# controller_rev1_1_flat.net
KiCad netlist of a schematic drawn in EAGLE
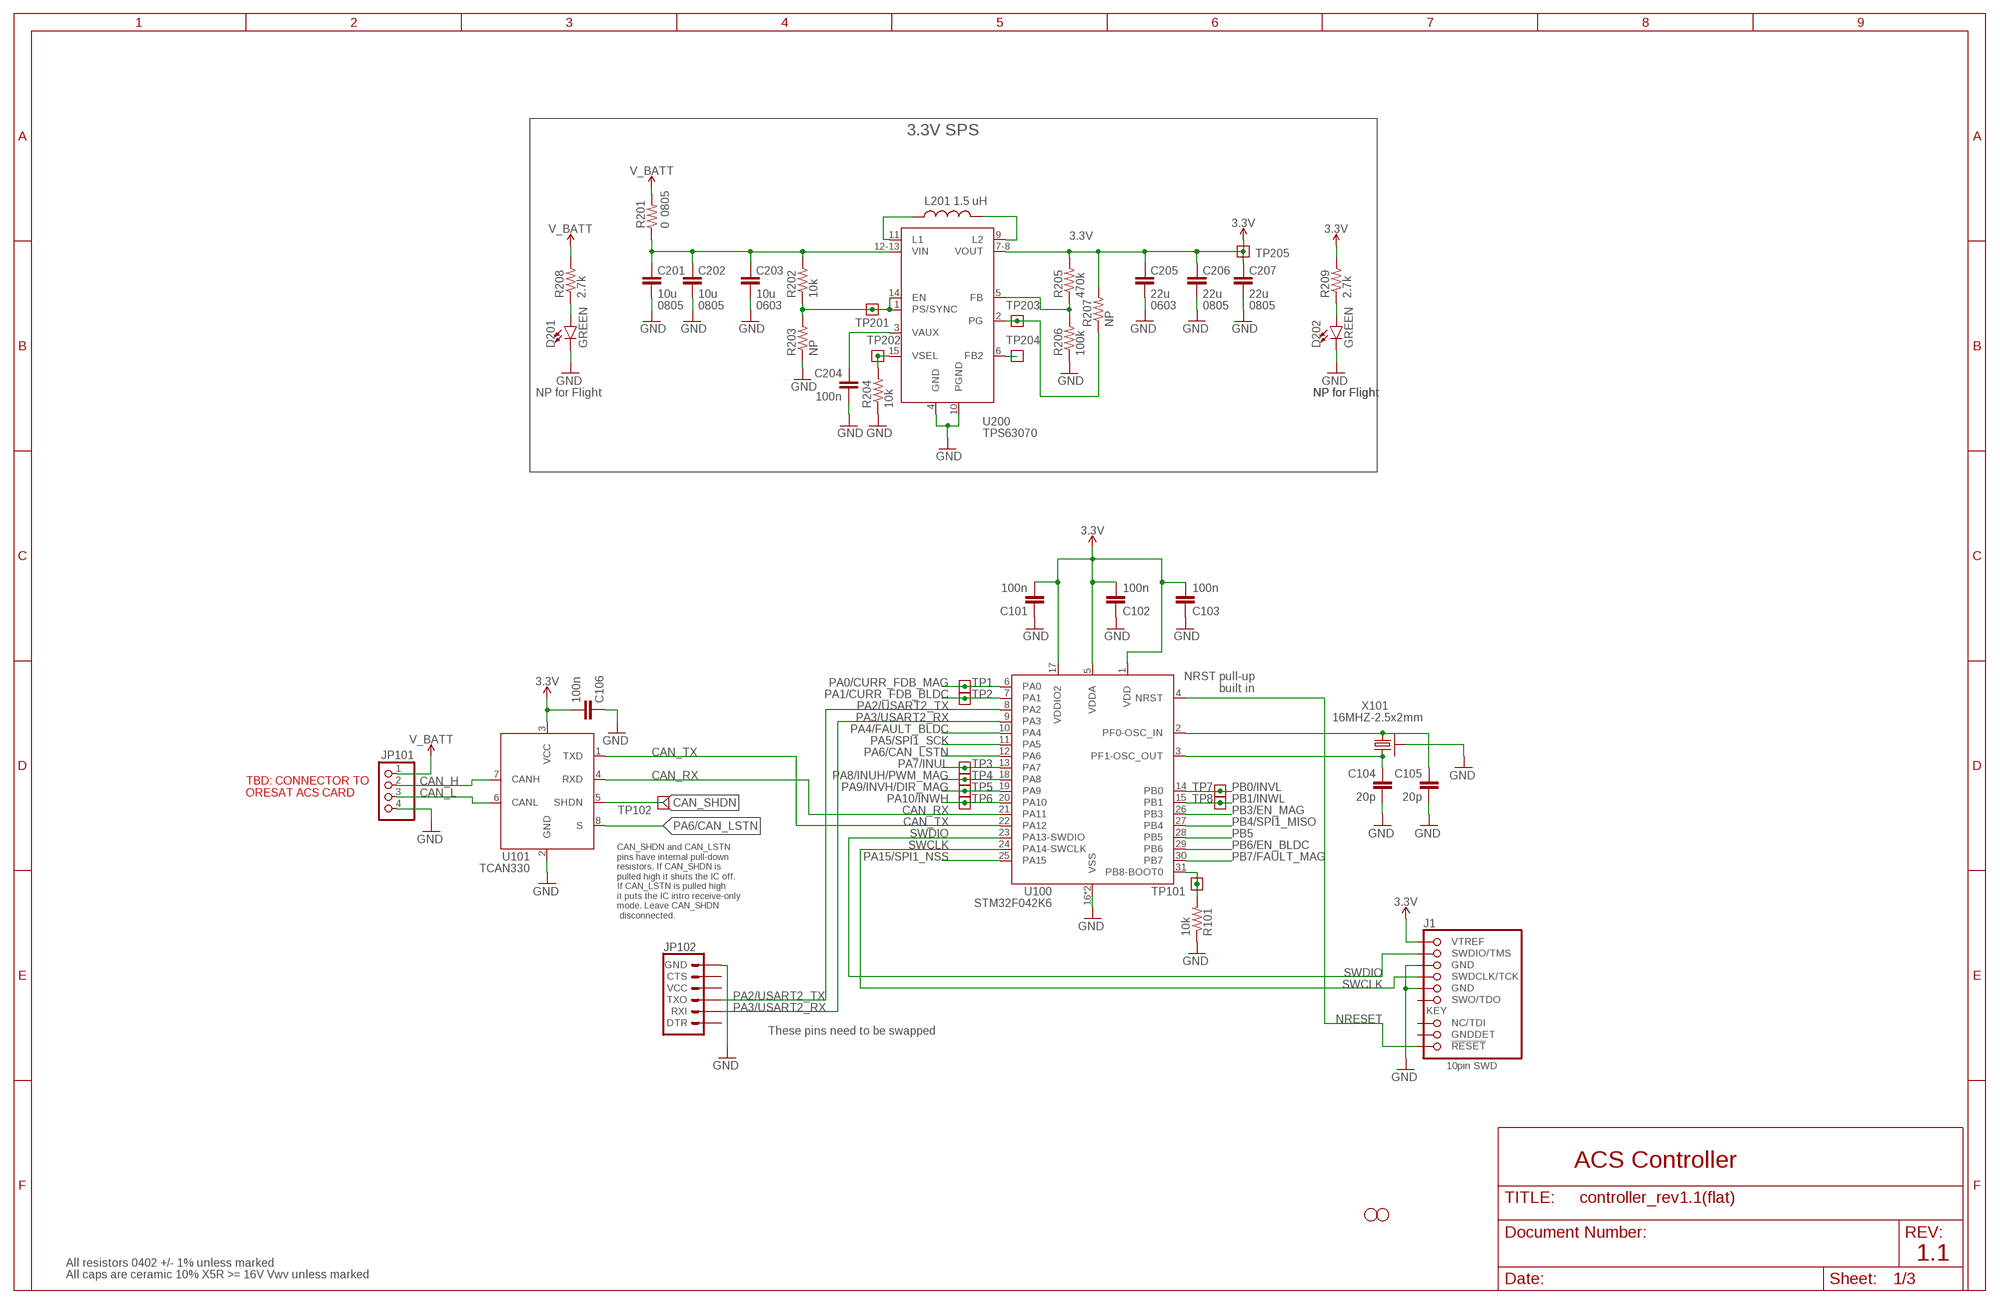
[diagram p0: schematic, sheet 1]
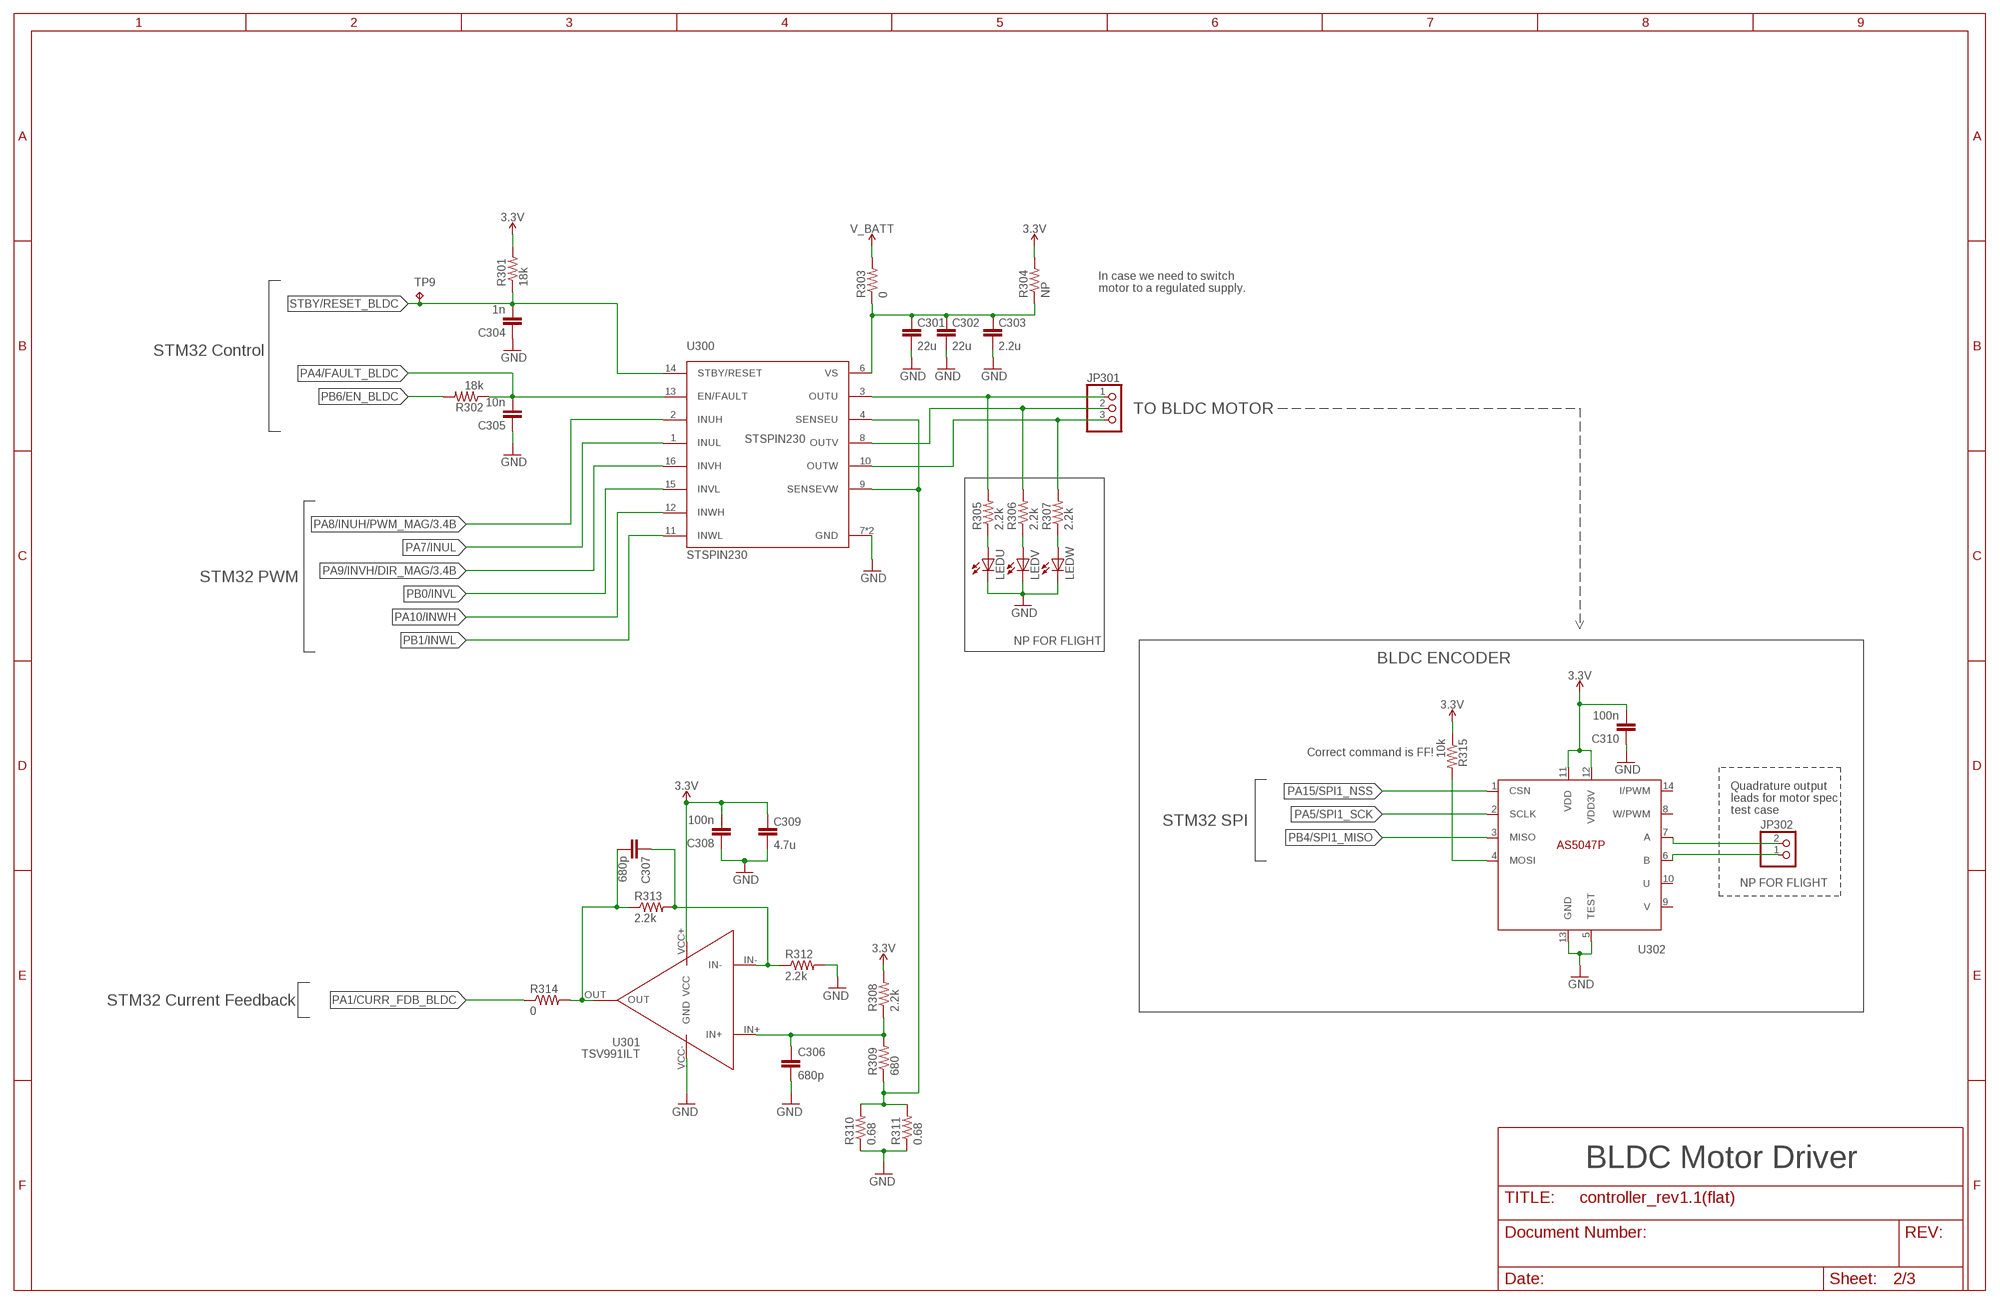
[diagram p1: schematic, sheet 2]
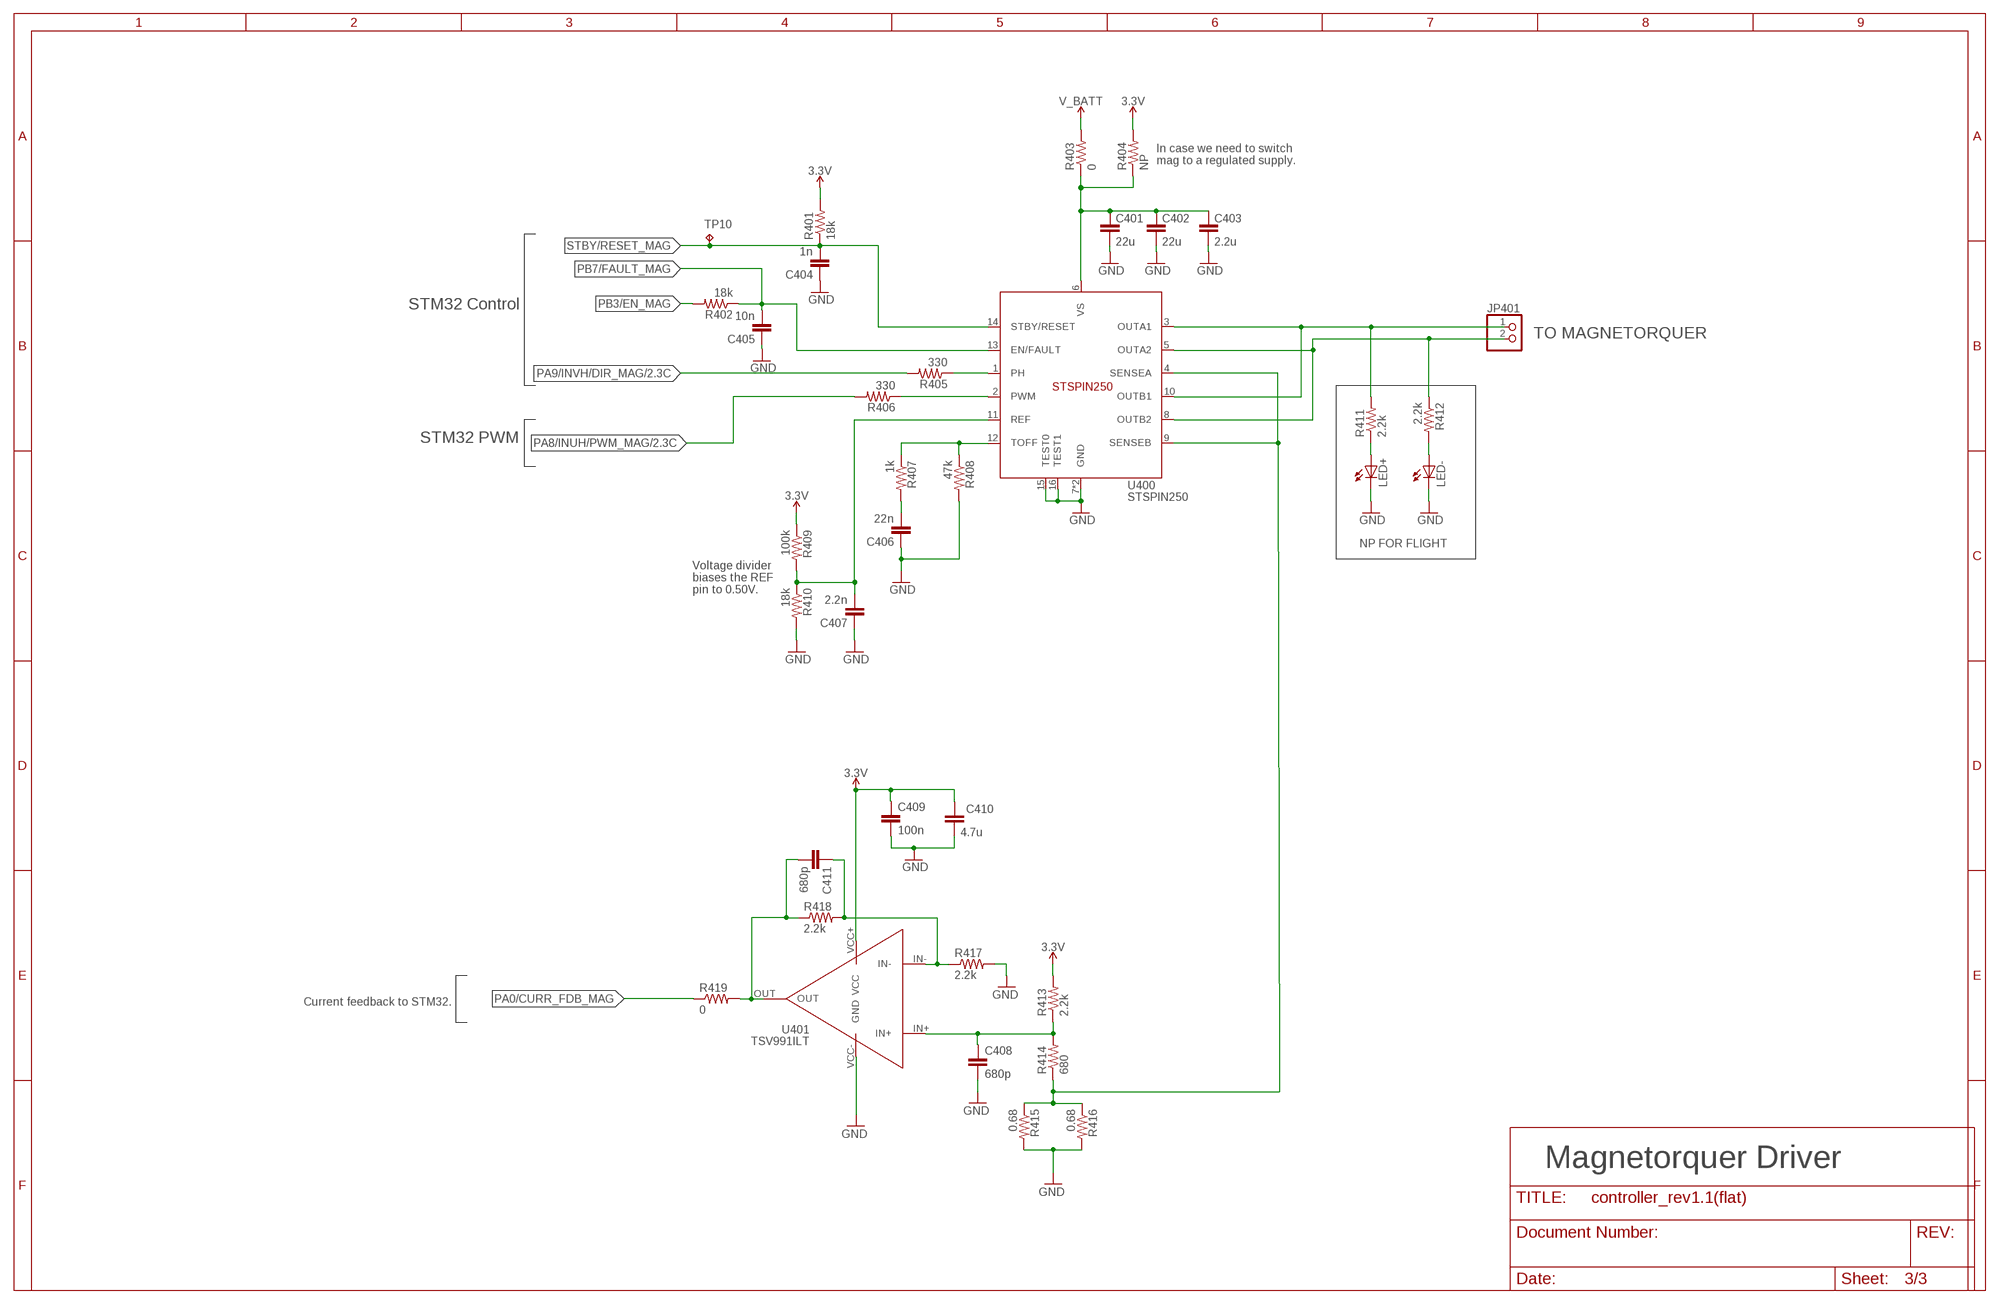
[diagram p2: schematic, sheet 3]

(export (version "E")
  (design (tool "Eeschema 10.0.6"))
  (components
    (comp (ref "C301")
      (value "22u")
      (footprint "eagle-import:.0603-B-NOSILK")
      (fields (field (name "MFR") "Samsung") (field (name "MPN") "CL05B104KO5NNNC"))
      (libsource (lib "eagle-import") (part "C-EU0603-B-NOSILK"))
    )
    (comp (ref "C302")
      (value "22u")
      (footprint "eagle-import:.0603-B-NOSILK")
      (fields (field (name "MFR") "Samsung") (field (name "MPN") "CL05B104KO5NNNC"))
      (libsource (lib "eagle-import") (part "C-EU0603-B-NOSILK"))
    )
    (comp (ref "C303")
      (value "2.2u")
      (footprint "eagle-import:.0603-B-NOSILK")
      (fields (field (name "MFR") "Samsung") (field (name "MPN") "CL05B104KO5NNNC"))
      (libsource (lib "eagle-import") (part "C-EU0603-B-NOSILK"))
    )
    (comp (ref "C304")
      (value "1n")
      (footprint "eagle-import:.0402-B-NOSILK")
      (fields (field (name "MFR") "Samsung") (field (name "MPN") "CL05B104KO5NNNC"))
      (libsource (lib "eagle-import") (part "rcl_custom_C-EU0402-B-NOSILK"))
    )
    (comp (ref "C305")
      (value "10n")
      (footprint "eagle-import:.0402-B-NOSILK")
      (fields (field (name "MFR") "Samsung") (field (name "MPN") "CL05B104KO5NNNC"))
      (libsource (lib "eagle-import") (part "rcl_custom_C-EU0402-B-NOSILK"))
    )
    (comp (ref "C306")
      (value "680p")
      (footprint "eagle-import:.0402-B-NOSILK")
      (fields (field (name "MFR") "Samsung") (field (name "MPN") "CL05B104KO5NNNC"))
      (libsource (lib "eagle-import") (part "rcl_custom_C-EU0402-B-NOSILK"))
    )
    (comp (ref "C307")
      (value "680p")
      (footprint "eagle-import:.0402-B-NOSILK")
      (fields (field (name "MFR") "Samsung") (field (name "MPN") "CL05B104KO5NNNC"))
      (libsource (lib "eagle-import") (part "rcl_custom_C-EU0402-B-NOSILK"))
    )
    (comp (ref "C308")
      (value "100n")
      (footprint "eagle-import:.0402-B-NOSILK")
      (fields (field (name "MFR") "Samsung") (field (name "MPN") "CL05B104KO5NNNC"))
      (libsource (lib "eagle-import") (part "rcl_custom_C-EU0402-B-NOSILK"))
    )
    (comp (ref "C309")
      (value "4.7u")
      (footprint "eagle-import:.0603-B-NOSILK")
      (fields (field (name "MFR") "Samsung") (field (name "MPN") "CL05B104KO5NNNC"))
      (libsource (lib "eagle-import") (part "C-EU0603-B-NOSILK"))
    )
    (comp (ref "C310")
      (value "100n")
      (footprint "eagle-import:.0402-B-NOSILK")
      (fields (field (name "MFR") "Samsung") (field (name "MPN") "CL05B104KO5NNNC"))
      (libsource (lib "eagle-import") (part "rcl_custom_C-EU0402-B-NOSILK"))
    )
    (comp (ref "JP301")
      (value "PINHD-1X3")
      (footprint "eagle-import:1X03")
      (libsource (lib "eagle-import") (part "PINHD-1X3"))
    )
    (comp (ref "JP302")
      (value "PINHD-1X2/90")
      (footprint "eagle-import:1X02_90")
      (libsource (lib "eagle-import") (part "PINHD-1X2/90"))
    )
    (comp (ref "LEDU")
      (value "LEDCHIP-LED0603")
      (footprint "eagle-import:CHIP-LED0603")
      (libsource (lib "eagle-import") (part "LEDCHIP-LED0603"))
    )
    (comp (ref "LEDV")
      (value "LEDCHIP-LED0603")
      (footprint "eagle-import:CHIP-LED0603")
      (libsource (lib "eagle-import") (part "LEDCHIP-LED0603"))
    )
    (comp (ref "LEDW")
      (value "LEDCHIP-LED0603")
      (footprint "eagle-import:CHIP-LED0603")
      (libsource (lib "eagle-import") (part "LEDCHIP-LED0603"))
    )
    (comp (ref "R301")
      (value "18k")
      (footprint "eagle-import:.0402-B-NOSILK")
      (fields (field (name "MFR") "Samsung") (field (name "MPN") "RC1005F6653CS"))
      (libsource (lib "eagle-import") (part "rcl_custom_R-US_0402-B-NOSILK"))
    )
    (comp (ref "R302")
      (value "18k")
      (footprint "eagle-import:.0402-B-NOSILK")
      (fields (field (name "MFR") "Samsung") (field (name "MPN") "RC1005F6653CS"))
      (libsource (lib "eagle-import") (part "rcl_custom_R-US_0402-B-NOSILK"))
    )
    (comp (ref "R303")
      (value "0")
      (footprint "eagle-import:.0805-B-NOSILK")
      (libsource (lib "eagle-import") (part "R-US_0805-B-NOSILK"))
    )
    (comp (ref "R304")
      (value "NP")
      (footprint "eagle-import:.0805-B-NOSILK")
      (libsource (lib "eagle-import") (part "R-US_0805-B-NOSILK"))
    )
    (comp (ref "R305")
      (value "2.2k")
      (footprint "eagle-import:.0805-B-NOSILK")
      (libsource (lib "eagle-import") (part "R-US_0805-B-NOSILK"))
    )
    (comp (ref "R306")
      (value "2.2k")
      (footprint "eagle-import:.0805-B-NOSILK")
      (libsource (lib "eagle-import") (part "R-US_0805-B-NOSILK"))
    )
    (comp (ref "R307")
      (value "2.2k")
      (footprint "eagle-import:.0805-B-NOSILK")
      (libsource (lib "eagle-import") (part "R-US_0805-B-NOSILK"))
    )
    (comp (ref "R308")
      (value "2.2k")
      (footprint "eagle-import:.0402-B-NOSILK")
      (fields (field (name "MFR") "Samsung") (field (name "MPN") "RC1005F6653CS"))
      (libsource (lib "eagle-import") (part "rcl_custom_R-US_0402-B-NOSILK"))
    )
    (comp (ref "R309")
      (value "680")
      (footprint "eagle-import:.0402-B-NOSILK")
      (fields (field (name "MFR") "Samsung") (field (name "MPN") "RC1005F6653CS"))
      (libsource (lib "eagle-import") (part "rcl_custom_R-US_0402-B-NOSILK"))
    )
    (comp (ref "R310")
      (value "0.68")
      (footprint "eagle-import:.0805-B-NOSILK")
      (libsource (lib "eagle-import") (part "R-US_0805-B-NOSILK"))
    )
    (comp (ref "R311")
      (value "0.68")
      (footprint "eagle-import:.0805-B-NOSILK")
      (libsource (lib "eagle-import") (part "R-US_0805-B-NOSILK"))
    )
    (comp (ref "R312")
      (value "2.2k")
      (footprint "eagle-import:.0402-B-NOSILK")
      (fields (field (name "MFR") "Samsung") (field (name "MPN") "RC1005F6653CS"))
      (libsource (lib "eagle-import") (part "rcl_custom_R-US_0402-B-NOSILK"))
    )
    (comp (ref "R313")
      (value "2.2k")
      (footprint "eagle-import:.0402-B-NOSILK")
      (fields (field (name "MFR") "Samsung") (field (name "MPN") "RC1005F6653CS"))
      (libsource (lib "eagle-import") (part "rcl_custom_R-US_0402-B-NOSILK"))
    )
    (comp (ref "R314")
      (value "0")
      (footprint "eagle-import:.0402-B-NOSILK")
      (fields (field (name "MFR") "Samsung") (field (name "MPN") "RC1005F6653CS"))
      (libsource (lib "eagle-import") (part "rcl_custom_R-US_0402-B-NOSILK"))
    )
    (comp (ref "R315")
      (value "10k")
      (footprint "eagle-import:.0402-B-NOSILK")
      (fields (field (name "MFR") "Samsung") (field (name "MPN") "RC1005F6653CS"))
      (libsource (lib "eagle-import") (part "rcl_custom_R-US_0402-B-NOSILK"))
    )
    (comp (ref "TP9")
      (value "TPPAD1-13")
      (footprint "eagle-import:P1-13")
      (libsource (lib "eagle-import") (part "TPPAD1-13"))
    )
    (comp (ref "U300")
      (value "STSPIN230")
      (footprint "eagle-import:VFQFPN")
      (libsource (lib "eagle-import") (part "STSPIN230"))
    )
    (comp (ref "U301")
      (value "TSV991ILT")
      (footprint "eagle-import:SOT23-5")
      (libsource (lib "eagle-import") (part "TSV991ILT"))
    )
    (comp (ref "U302")
      (value "AS5047P")
      (footprint "eagle-import:TSSOP14")
      (libsource (lib "eagle-import") (part "AS5047P"))
    )
    (comp (ref "C401")
      (value "22u")
      (footprint "eagle-import:.0603-B-NOSILK")
      (fields (field (name "MFR") "Samsung") (field (name "MPN") "CL05B104KO5NNNC"))
      (libsource (lib "eagle-import") (part "C-EU0603-B-NOSILK"))
    )
    (comp (ref "C402")
      (value "22u")
      (footprint "eagle-import:.0603-B-NOSILK")
      (fields (field (name "MFR") "Samsung") (field (name "MPN") "CL05B104KO5NNNC"))
      (libsource (lib "eagle-import") (part "C-EU0603-B-NOSILK"))
    )
    (comp (ref "C403")
      (value "2.2u")
      (footprint "eagle-import:.0603-B-NOSILK")
      (fields (field (name "MFR") "Samsung") (field (name "MPN") "CL05B104KO5NNNC"))
      (libsource (lib "eagle-import") (part "C-EU0603-B-NOSILK"))
    )
    (comp (ref "C404")
      (value "1n")
      (footprint "eagle-import:.0402-B-NOSILK")
      (fields (field (name "MFR") "Samsung") (field (name "MPN") "CL05B104KO5NNNC"))
      (libsource (lib "eagle-import") (part "rcl_custom_C-EU0402-B-NOSILK"))
    )
    (comp (ref "C405")
      (value "10n")
      (footprint "eagle-import:.0402-B-NOSILK")
      (fields (field (name "MFR") "Samsung") (field (name "MPN") "CL05B104KO5NNNC"))
      (libsource (lib "eagle-import") (part "rcl_custom_C-EU0402-B-NOSILK"))
    )
    (comp (ref "C406")
      (value "22n")
      (footprint "eagle-import:.0402-B-NOSILK")
      (fields (field (name "MFR") "Samsung") (field (name "MPN") "CL05B104KO5NNNC"))
      (libsource (lib "eagle-import") (part "rcl_custom_C-EU0402-B-NOSILK"))
    )
    (comp (ref "C407")
      (value "2.2n")
      (footprint "eagle-import:.0402-B-NOSILK")
      (fields (field (name "MFR") "Samsung") (field (name "MPN") "CL05B104KO5NNNC"))
      (libsource (lib "eagle-import") (part "rcl_custom_C-EU0402-B-NOSILK"))
    )
    (comp (ref "C408")
      (value "680p")
      (footprint "eagle-import:.0402-B-NOSILK")
      (fields (field (name "MFR") "Samsung") (field (name "MPN") "CL05B104KO5NNNC"))
      (libsource (lib "eagle-import") (part "rcl_custom_C-EU0402-B-NOSILK"))
    )
    (comp (ref "C409")
      (value "100n")
      (footprint "eagle-import:.0402-B-NOSILK")
      (fields (field (name "MFR") "Samsung") (field (name "MPN") "CL05B104KO5NNNC"))
      (libsource (lib "eagle-import") (part "rcl_custom_C-EU0402-B-NOSILK"))
    )
    (comp (ref "C410")
      (value "4.7u")
      (footprint "eagle-import:.0603-B-NOSILK")
      (fields (field (name "MFR") "Samsung") (field (name "MPN") "CL05B104KO5NNNC"))
      (libsource (lib "eagle-import") (part "C-EU0603-B-NOSILK"))
    )
    (comp (ref "C411")
      (value "680p")
      (footprint "eagle-import:.0402-B-NOSILK")
      (fields (field (name "MFR") "Samsung") (field (name "MPN") "CL05B104KO5NNNC"))
      (libsource (lib "eagle-import") (part "rcl_custom_C-EU0402-B-NOSILK"))
    )
    (comp (ref "JP401")
      (value "PINHD-1X2")
      (footprint "eagle-import:1X02")
      (libsource (lib "eagle-import") (part "PINHD-1X2"))
    )
    (comp (ref "LED+")
      (value "LEDCHIP-LED0603")
      (footprint "eagle-import:CHIP-LED0603")
      (libsource (lib "eagle-import") (part "LEDCHIP-LED0603"))
    )
    (comp (ref "LED-")
      (value "LEDCHIP-LED0603")
      (footprint "eagle-import:CHIP-LED0603")
      (libsource (lib "eagle-import") (part "LEDCHIP-LED0603"))
    )
    (comp (ref "R401")
      (value "18k")
      (footprint "eagle-import:.0402-B-NOSILK")
      (fields (field (name "MFR") "Samsung") (field (name "MPN") "RC1005F6653CS"))
      (libsource (lib "eagle-import") (part "rcl_custom_R-US_0402-B-NOSILK"))
    )
    (comp (ref "R402")
      (value "18k")
      (footprint "eagle-import:.0402-B-NOSILK")
      (fields (field (name "MFR") "Samsung") (field (name "MPN") "RC1005F6653CS"))
      (libsource (lib "eagle-import") (part "rcl_custom_R-US_0402-B-NOSILK"))
    )
    (comp (ref "R403")
      (value "0")
      (footprint "eagle-import:.0805-B-NOSILK")
      (libsource (lib "eagle-import") (part "R-US_0805-B-NOSILK"))
    )
    (comp (ref "R404")
      (value "NP")
      (footprint "eagle-import:.0805-B-NOSILK")
      (libsource (lib "eagle-import") (part "R-US_0805-B-NOSILK"))
    )
    (comp (ref "R405")
      (value "330")
      (footprint "eagle-import:.0402-B-NOSILK")
      (fields (field (name "MFR") "Samsung") (field (name "MPN") "RC1005F6653CS"))
      (libsource (lib "eagle-import") (part "rcl_custom_R-US_0402-B-NOSILK"))
    )
    (comp (ref "R406")
      (value "330")
      (footprint "eagle-import:.0402-B-NOSILK")
      (fields (field (name "MFR") "Samsung") (field (name "MPN") "RC1005F6653CS"))
      (libsource (lib "eagle-import") (part "rcl_custom_R-US_0402-B-NOSILK"))
    )
    (comp (ref "R407")
      (value "1k")
      (footprint "eagle-import:.0402-B-NOSILK")
      (fields (field (name "MFR") "Samsung") (field (name "MPN") "RC1005F6653CS"))
      (libsource (lib "eagle-import") (part "rcl_custom_R-US_0402-B-NOSILK"))
    )
    (comp (ref "R408")
      (value "47k")
      (footprint "eagle-import:.0402-B-NOSILK")
      (fields (field (name "MFR") "Samsung") (field (name "MPN") "RC1005F6653CS"))
      (libsource (lib "eagle-import") (part "rcl_custom_R-US_0402-B-NOSILK"))
    )
    (comp (ref "R409")
      (value "100k")
      (footprint "eagle-import:.0402-B-NOSILK")
      (fields (field (name "MFR") "Samsung") (field (name "MPN") "RC1005F6653CS"))
      (libsource (lib "eagle-import") (part "rcl_custom_R-US_0402-B-NOSILK"))
    )
    (comp (ref "R410")
      (value "18k")
      (footprint "eagle-import:.0402-B-NOSILK")
      (fields (field (name "MFR") "Samsung") (field (name "MPN") "RC1005F6653CS"))
      (libsource (lib "eagle-import") (part "rcl_custom_R-US_0402-B-NOSILK"))
    )
    (comp (ref "R411")
      (value "2.2k")
      (footprint "eagle-import:.0805-B-NOSILK")
      (libsource (lib "eagle-import") (part "R-US_0805-B-NOSILK"))
    )
    (comp (ref "R412")
      (value "2.2k")
      (footprint "eagle-import:.0805-B-NOSILK")
      (libsource (lib "eagle-import") (part "R-US_0805-B-NOSILK"))
    )
    (comp (ref "R413")
      (value "2.2k")
      (footprint "eagle-import:.0402-B-NOSILK")
      (fields (field (name "MFR") "Samsung") (field (name "MPN") "RC1005F6653CS"))
      (libsource (lib "eagle-import") (part "rcl_custom_R-US_0402-B-NOSILK"))
    )
    (comp (ref "R414")
      (value "680")
      (footprint "eagle-import:.0402-B-NOSILK")
      (fields (field (name "MFR") "Samsung") (field (name "MPN") "RC1005F6653CS"))
      (libsource (lib "eagle-import") (part "rcl_custom_R-US_0402-B-NOSILK"))
    )
    (comp (ref "R415")
      (value "0.68")
      (footprint "eagle-import:.0805-B-NOSILK")
      (libsource (lib "eagle-import") (part "R-US_0805-B-NOSILK"))
    )
    (comp (ref "R416")
      (value "0.68")
      (footprint "eagle-import:.0805-B-NOSILK")
      (libsource (lib "eagle-import") (part "R-US_0805-B-NOSILK"))
    )
    (comp (ref "R417")
      (value "2.2k")
      (footprint "eagle-import:.0402-B-NOSILK")
      (fields (field (name "MFR") "Samsung") (field (name "MPN") "RC1005F6653CS"))
      (libsource (lib "eagle-import") (part "rcl_custom_R-US_0402-B-NOSILK"))
    )
    (comp (ref "R418")
      (value "2.2k")
      (footprint "eagle-import:.0402-B-NOSILK")
      (fields (field (name "MFR") "Samsung") (field (name "MPN") "RC1005F6653CS"))
      (libsource (lib "eagle-import") (part "rcl_custom_R-US_0402-B-NOSILK"))
    )
    (comp (ref "R419")
      (value "0")
      (footprint "eagle-import:.0402-B-NOSILK")
      (fields (field (name "MFR") "Samsung") (field (name "MPN") "RC1005F6653CS"))
      (libsource (lib "eagle-import") (part "rcl_custom_R-US_0402-B-NOSILK"))
    )
    (comp (ref "TP10")
      (value "TPPAD1-13")
      (footprint "eagle-import:P1-13")
      (libsource (lib "eagle-import") (part "TPPAD1-13"))
    )
    (comp (ref "U400")
      (value "STSPIN250")
      (footprint "eagle-import:VFQPN")
      (libsource (lib "eagle-import") (part "STSPIN250"))
    )
    (comp (ref "U401")
      (value "TSV991ILT")
      (footprint "eagle-import:SOT23-5")
      (libsource (lib "eagle-import") (part "TSV991ILT"))
    )
    (comp (ref "C101")
      (value "100n")
      (footprint "eagle-import:.0402-B-NOSILK")
      (fields (field (name "MFR") "Samsung") (field (name "MPN") "CL05B104KO5NNNC"))
      (libsource (lib "eagle-import") (part "rcl_custom_C-EU0402-B-NOSILK"))
    )
    (comp (ref "C102")
      (value "100n")
      (footprint "eagle-import:.0402-B-NOSILK")
      (fields (field (name "MFR") "Samsung") (field (name "MPN") "CL05B104KO5NNNC"))
      (libsource (lib "eagle-import") (part "rcl_custom_C-EU0402-B-NOSILK"))
    )
    (comp (ref "C103")
      (value "100n")
      (footprint "eagle-import:.0402-B-NOSILK")
      (fields (field (name "MFR") "Samsung") (field (name "MPN") "CL05B104KO5NNNC"))
      (libsource (lib "eagle-import") (part "rcl_custom_C-EU0402-B-NOSILK"))
    )
    (comp (ref "C104")
      (value "20p")
      (footprint "eagle-import:.0402-B-NOSILK")
      (fields (field (name "MFR") "Samsung") (field (name "MPN") "CL05C200JB51PNC"))
      (libsource (lib "eagle-import") (part "rcl_custom_C-EU0402-B-NOSILK"))
    )
    (comp (ref "C105")
      (value "20p")
      (footprint "eagle-import:.0402-B-NOSILK")
      (fields (field (name "MFR") "Samsung") (field (name "MPN") "CL05C200JB51PNC"))
      (libsource (lib "eagle-import") (part "rcl_custom_C-EU0402-B-NOSILK"))
    )
    (comp (ref "C106")
      (value "100n")
      (footprint "eagle-import:.0402-B-NOSILK")
      (fields (field (name "MFR") "Samsung") (field (name "MPN") "CL05B104KO5NNNC"))
      (libsource (lib "eagle-import") (part "rcl_custom_C-EU0402-B-NOSILK"))
    )
    (comp (ref "C201")
      (value "10u")
      (footprint "eagle-import:.0805-B-NOSILK")
      (libsource (lib "eagle-import") (part "C-EU0805-B-NOSILK"))
    )
    (comp (ref "C202")
      (value "10u")
      (footprint "eagle-import:.0805-B-NOSILK")
      (libsource (lib "eagle-import") (part "C-EU0805-B-NOSILK"))
    )
    (comp (ref "C203")
      (value "10u")
      (footprint "eagle-import:.0603-B-NOSILK")
      (fields (field (name "MFR") "Samsung") (field (name "MPN") "CL05B104KO5NNNC"))
      (libsource (lib "eagle-import") (part "C-EU0603-B-NOSILK"))
    )
    (comp (ref "C204")
      (value "100n")
      (footprint "eagle-import:.0402-B-NOSILK")
      (fields (field (name "MFR") "Samsung") (field (name "MPN") "CL05B104KO5NNNC"))
      (libsource (lib "eagle-import") (part "rcl_custom_C-EU0402-B-NOSILK"))
    )
    (comp (ref "C205")
      (value "22u")
      (footprint "eagle-import:.0603-B-NOSILK")
      (fields (field (name "MFR") "Samsung") (field (name "MPN") "CL05B104KO5NNNC"))
      (libsource (lib "eagle-import") (part "C-EU0603-B-NOSILK"))
    )
    (comp (ref "C206")
      (value "22u")
      (footprint "eagle-import:.0805-B-NOSILK")
      (libsource (lib "eagle-import") (part "C-EU0805-B-NOSILK"))
    )
    (comp (ref "C207")
      (value "22u")
      (footprint "eagle-import:.0805-B-NOSILK")
      (libsource (lib "eagle-import") (part "C-EU0805-B-NOSILK"))
    )
    (comp (ref "D201")
      (value "GREEN")
      (footprint "eagle-import:LED-0603")
      (libsource (lib "eagle-import") (part "LED-GREEN0603"))
    )
    (comp (ref "D202")
      (value "GREEN")
      (footprint "eagle-import:LED-0603")
      (libsource (lib "eagle-import") (part "LED-GREEN0603"))
    )
    (comp (ref "H1")
      (value "STAND-OFFTIGHT")
      (footprint "eagle-import:STAND-OFF-TIGHT")
      (libsource (lib "eagle-import") (part "STAND-OFFTIGHT"))
    )
    (comp (ref "H2")
      (value "STAND-OFFTIGHT")
      (footprint "eagle-import:STAND-OFF-TIGHT")
      (libsource (lib "eagle-import") (part "STAND-OFFTIGHT"))
    )
    (comp (ref "J1")
      (value "1.27MM-SWD-CONNECTOR")
      (footprint "eagle-import:1.27MM_2X5")
      (libsource (lib "eagle-import") (part "1.27MM-SWD-CONNECTOR"))
    )
    (comp (ref "JP101")
      (value "PINHD-1X4")
      (footprint "eagle-import:1X04")
      (libsource (lib "eagle-import") (part "PINHD-1X4"))
    )
    (comp (ref "JP102")
      (value "6_PIN_SERIAL_TARGETSILK")
      (footprint "eagle-import:6_PIN_SERIAL_TARGET_SIDE_W_SILK")
      (libsource (lib "eagle-import") (part "6_PIN_SERIAL_TARGETSILK"))
    )
    (comp (ref "L201")
      (value "1.5 uH")
      (footprint "eagle-import:L-COILCRAFT-XFL4020")
      (fields (field (name "MFR") "Coilcraft") (field (name "MPN") "XFL4020-152ME"))
      (libsource (lib "eagle-import") (part "L-COILCRAFT-XFL4020"))
    )
    (comp (ref "R101")
      (value "10k")
      (footprint "eagle-import:.0402-B-NOSILK")
      (fields (field (name "MFR") "Samsung") (field (name "MPN") "RC1005F6653CS"))
      (libsource (lib "eagle-import") (part "rcl_custom_R-US_0402-B-NOSILK"))
    )
    (comp (ref "R201")
      (value "0")
      (footprint "eagle-import:.0805-B-NOSILK")
      (fields (field (name "MFR") "Rohm") (field (name "MPN") "MCR10EZPJ000"))
      (libsource (lib "eagle-import") (part "rcl_custom_R-US_0805-B-NOSILK"))
    )
    (comp (ref "R202")
      (value "10k")
      (footprint "eagle-import:.0402-B-NOSILK")
      (fields (field (name "MFR") "Samsung") (field (name "MPN") "RC1005F6653CS"))
      (libsource (lib "eagle-import") (part "rcl_custom_R-US_0402-B-NOSILK"))
    )
    (comp (ref "R203")
      (value "NP")
      (footprint "eagle-import:.0402-B-NOSILK")
      (fields (field (name "MFR") "Samsung") (field (name "MPN") "RC1005F6653CS"))
      (libsource (lib "eagle-import") (part "rcl_custom_R-US_0402-B-NOSILK"))
    )
    (comp (ref "R204")
      (value "10k")
      (footprint "eagle-import:.0402-B-NOSILK")
      (fields (field (name "MFR") "Samsung") (field (name "MPN") "RC1005F6653CS"))
      (libsource (lib "eagle-import") (part "rcl_custom_R-US_0402-B-NOSILK"))
    )
    (comp (ref "R205")
      (value "470k")
      (footprint "eagle-import:.0402-B-NOSILK")
      (fields (field (name "MFR") "Samsung") (field (name "MPN") "RC1005F6653CS"))
      (libsource (lib "eagle-import") (part "rcl_custom_R-US_0402-B-NOSILK"))
    )
    (comp (ref "R206")
      (value "100k")
      (footprint "eagle-import:.0402-B-NOSILK")
      (fields (field (name "MFR") "Samsung") (field (name "MPN") "RC1005F6653CS"))
      (libsource (lib "eagle-import") (part "rcl_custom_R-US_0402-B-NOSILK"))
    )
    (comp (ref "R207")
      (value "NP")
      (footprint "eagle-import:.0402-B-NOSILK")
      (fields (field (name "MFR") "Samsung") (field (name "MPN") "RC1005F6653CS"))
      (libsource (lib "eagle-import") (part "rcl_custom_R-US_0402-B-NOSILK"))
    )
    (comp (ref "R208")
      (value "2.7k")
      (footprint "eagle-import:.0402-B-NOSILK")
      (fields (field (name "MFR") "Samsung") (field (name "MPN") "RC1005F6653CS"))
      (libsource (lib "eagle-import") (part "rcl_custom_R-US_0402-B-NOSILK"))
    )
    (comp (ref "R209")
      (value "2.7k")
      (footprint "eagle-import:.0402-B-NOSILK")
      (fields (field (name "MFR") "Samsung") (field (name "MPN") "RC1005F6653CS"))
      (libsource (lib "eagle-import") (part "rcl_custom_R-US_0402-B-NOSILK"))
    )
    (comp (ref "TP1")
      (value "TEST-POINT")
      (footprint "eagle-import:2MM-TEST-POINT")
      (libsource (lib "eagle-import") (part "TEST-POINT"))
    )
    (comp (ref "TP2")
      (value "TEST-POINT")
      (footprint "eagle-import:2MM-TEST-POINT")
      (libsource (lib "eagle-import") (part "TEST-POINT"))
    )
    (comp (ref "TP3")
      (value "TEST-POINT")
      (footprint "eagle-import:2MM-TEST-POINT")
      (libsource (lib "eagle-import") (part "TEST-POINT"))
    )
    (comp (ref "TP4")
      (value "TEST-POINT")
      (footprint "eagle-import:2MM-TEST-POINT")
      (libsource (lib "eagle-import") (part "TEST-POINT"))
    )
    (comp (ref "TP5")
      (value "TEST-POINT")
      (footprint "eagle-import:2MM-TEST-POINT")
      (libsource (lib "eagle-import") (part "TEST-POINT"))
    )
    (comp (ref "TP6")
      (value "TEST-POINT")
      (footprint "eagle-import:2MM-TEST-POINT")
      (libsource (lib "eagle-import") (part "TEST-POINT"))
    )
    (comp (ref "TP7")
      (value "TEST-POINT")
      (footprint "eagle-import:2MM-TEST-POINT")
      (libsource (lib "eagle-import") (part "TEST-POINT"))
    )
    (comp (ref "TP8")
      (value "TEST-POINT")
      (footprint "eagle-import:2MM-TEST-POINT")
      (libsource (lib "eagle-import") (part "TEST-POINT"))
    )
    (comp (ref "TP101")
      (value "TEST-POINT")
      (footprint "eagle-import:2MM-TEST-POINT")
      (libsource (lib "eagle-import") (part "TEST-POINT"))
    )
    (comp (ref "TP102")
      (value "TEST-POINT")
      (footprint "eagle-import:2MM-TEST-POINT")
      (libsource (lib "eagle-import") (part "TEST-POINT"))
    )
    (comp (ref "TP201")
      (value "TEST-POINT")
      (footprint "eagle-import:2MM-TEST-POINT")
      (libsource (lib "eagle-import") (part "TEST-POINT"))
    )
    (comp (ref "TP202")
      (value "TEST-POINT")
      (footprint "eagle-import:2MM-TEST-POINT")
      (libsource (lib "eagle-import") (part "TEST-POINT"))
    )
    (comp (ref "TP203")
      (value "TEST-POINT")
      (footprint "eagle-import:2MM-TEST-POINT")
      (libsource (lib "eagle-import") (part "TEST-POINT"))
    )
    (comp (ref "TP204")
      (value "TEST-POINT")
      (footprint "eagle-import:2MM-TEST-POINT")
      (libsource (lib "eagle-import") (part "TEST-POINT"))
    )
    (comp (ref "TP205")
      (value "TEST-POINT")
      (footprint "eagle-import:2MM-TEST-POINT")
      (libsource (lib "eagle-import") (part "TEST-POINT"))
    )
    (comp (ref "U100")
      (value "STM32F042K6")
      (footprint "eagle-import:QFP32-7X7")
      (fields (field (name "MFR") "STMicroelectronics") (field (name "MPN") "STM32F042K6T7"))
      (libsource (lib "eagle-import") (part "STM32F042K6"))
    )
    (comp (ref "U101")
      (value "TCAN330")
      (footprint "eagle-import:SOT23-8_TI-DCN")
      (fields (field (name "MFR") "Texas Instruments") (field (name "MPN") "TCAN330GDCNT"))
      (libsource (lib "eagle-import") (part "TCAN330"))
    )
    (comp (ref "U200")
      (value "TPS63070")
      (footprint "eagle-import:TPS63070X")
      (libsource (lib "eagle-import") (part "TPS63070X"))
    )
    (comp (ref "X101")
      (value "16MHZ-2.5x2mm")
      (footprint "eagle-import:CRYSTAL_2.5X2")
      (fields (field (name "MFR") "ECS Inc.") (field (name "MPN") "ECS-160-10-36Q-ES-TR"))
      (libsource (lib "eagle-import") (part "CRYSTAL-WITH-GND"))
    )
  )
  (nets
    (net (code "1") (name "3.3V") (class "Default")
      (node (ref "C101") (pin "2") (pinfunction "2_2") (pintype "passive"))
      (node (ref "C102") (pin "2") (pinfunction "2_2") (pintype "passive"))
      (node (ref "C103") (pin "2") (pinfunction "2_2") (pintype "passive"))
      (node (ref "C106") (pin "2") (pinfunction "2_2") (pintype "passive"))
      (node (ref "C205") (pin "1") (pinfunction "1_1") (pintype "passive"))
      (node (ref "C206") (pin "1") (pinfunction "1_1") (pintype "passive"))
      (node (ref "C207") (pin "1") (pinfunction "1_1") (pintype "passive"))
      (node (ref "C308") (pin "2") (pinfunction "2_2") (pintype "passive"))
      (node (ref "C309") (pin "1") (pinfunction "1_1") (pintype "passive"))
      (node (ref "C310") (pin "2") (pinfunction "2_2") (pintype "passive"))
      (node (ref "C409") (pin "1") (pinfunction "1_1") (pintype "passive"))
      (node (ref "C410") (pin "1") (pinfunction "1_1") (pintype "passive"))
      (node (ref "J1") (pin "VTREF") (pinfunction "VTREF_VTREF") (pintype "passive"))
      (node (ref "R205") (pin "2") (pinfunction "2_2") (pintype "passive"))
      (node (ref "R207") (pin "2") (pinfunction "2_2") (pintype "passive"))
      (node (ref "R209") (pin "2") (pinfunction "2_2") (pintype "passive"))
      (node (ref "R301") (pin "2") (pinfunction "2_2") (pintype "passive"))
      (node (ref "R304") (pin "2") (pinfunction "2_2") (pintype "passive"))
      (node (ref "R308") (pin "2") (pinfunction "2_2") (pintype "passive"))
      (node (ref "R315") (pin "1") (pinfunction "1_1") (pintype "passive"))
      (node (ref "R401") (pin "2") (pinfunction "2_2") (pintype "passive"))
      (node (ref "R404") (pin "2") (pinfunction "2_2") (pintype "passive"))
      (node (ref "R409") (pin "1") (pinfunction "1_1") (pintype "passive"))
      (node (ref "R413") (pin "2") (pinfunction "2_2") (pintype "passive"))
      (node (ref "TP205") (pin "1") (pinfunction "1_1") (pintype "passive"))
      (node (ref "U100") (pin "1") (pinfunction "VDD_1") (pintype "power_in"))
      (node (ref "U100") (pin "17") (pinfunction "VDDIO2_17") (pintype "power_in"))
      (node (ref "U100") (pin "5") (pinfunction "VDDA_5") (pintype "power_in"))
      (node (ref "U101") (pin "3") (pinfunction "VCC_3") (pintype "power_in"))
      (node (ref "U200") (pin "7-8") (pinfunction "VOUT_7-8") (pintype "power_in"))
      (node (ref "U301") (pin "VCC+") (pinfunction "VCC_VCC+") (pintype "bidirectional"))
      (node (ref "U302") (pin "11") (pinfunction "VDD_11") (pintype "power_in"))
      (node (ref "U302") (pin "12") (pinfunction "VDD3V_12") (pintype "power_in"))
      (node (ref "U401") (pin "VCC+") (pinfunction "VCC_VCC+") (pintype "bidirectional"))
    )
    (net (code "2") (name "CAN_H") (class "Default")
      (node (ref "JP101") (pin "2") (pinfunction "2_2") (pintype "passive"))
      (node (ref "U101") (pin "7") (pinfunction "CANH_7") (pintype "bidirectional"))
    )
    (net (code "3") (name "CAN_L") (class "Default")
      (node (ref "JP101") (pin "3") (pinfunction "3_3") (pintype "passive"))
      (node (ref "U101") (pin "6") (pinfunction "CANL_6") (pintype "bidirectional"))
    )
    (net (code "4") (name "CAN_RX") (class "Default")
      (node (ref "U100") (pin "21") (pinfunction "PA11_21") (pintype "bidirectional"))
      (node (ref "U101") (pin "4") (pinfunction "RXD_4") (pintype "output"))
    )
    (net (code "5") (name "CAN_SHDN") (class "Default")
      (node (ref "TP102") (pin "1") (pinfunction "1_1") (pintype "passive"))
      (node (ref "U101") (pin "5") (pinfunction "SHDN_5") (pintype "input"))
    )
    (net (code "6") (name "CAN_TX") (class "Default")
      (node (ref "U100") (pin "22") (pinfunction "PA12_22") (pintype "bidirectional"))
      (node (ref "U101") (pin "1") (pinfunction "TXD_1") (pintype "input"))
    )
    (net (code "7") (name "GND") (class "Default")
      (node (ref "C101") (pin "1") (pinfunction "1_1") (pintype "passive"))
      (node (ref "C102") (pin "1") (pinfunction "1_1") (pintype "passive"))
      (node (ref "C103") (pin "1") (pinfunction "1_1") (pintype "passive"))
      (node (ref "C104") (pin "2") (pinfunction "2_2") (pintype "passive"))
      (node (ref "C105") (pin "2") (pinfunction "2_2") (pintype "passive"))
      (node (ref "C106") (pin "1") (pinfunction "1_1") (pintype "passive"))
      (node (ref "C201") (pin "2") (pinfunction "2_2") (pintype "passive"))
      (node (ref "C202") (pin "2") (pinfunction "2_2") (pintype "passive"))
      (node (ref "C203") (pin "2") (pinfunction "2_2") (pintype "passive"))
      (node (ref "C204") (pin "2") (pinfunction "2_2") (pintype "passive"))
      (node (ref "C205") (pin "2") (pinfunction "2_2") (pintype "passive"))
      (node (ref "C206") (pin "2") (pinfunction "2_2") (pintype "passive"))
      (node (ref "C207") (pin "2") (pinfunction "2_2") (pintype "passive"))
      (node (ref "C301") (pin "2") (pinfunction "2_2") (pintype "passive"))
      (node (ref "C302") (pin "2") (pinfunction "2_2") (pintype "passive"))
      (node (ref "C303") (pin "2") (pinfunction "2_2") (pintype "passive"))
      (node (ref "C304") (pin "1") (pinfunction "1_1") (pintype "passive"))
      (node (ref "C305") (pin "1") (pinfunction "1_1") (pintype "passive"))
      (node (ref "C306") (pin "2") (pinfunction "2_2") (pintype "passive"))
      (node (ref "C308") (pin "1") (pinfunction "1_1") (pintype "passive"))
      (node (ref "C309") (pin "2") (pinfunction "2_2") (pintype "passive"))
      (node (ref "C310") (pin "1") (pinfunction "1_1") (pintype "passive"))
      (node (ref "C401") (pin "2") (pinfunction "2_2") (pintype "passive"))
      (node (ref "C402") (pin "2") (pinfunction "2_2") (pintype "passive"))
      (node (ref "C403") (pin "2") (pinfunction "2_2") (pintype "passive"))
      (node (ref "C404") (pin "1") (pinfunction "1_1") (pintype "passive"))
      (node (ref "C405") (pin "1") (pinfunction "1_1") (pintype "passive"))
      (node (ref "C406") (pin "1") (pinfunction "1_1") (pintype "passive"))
      (node (ref "C407") (pin "1") (pinfunction "1_1") (pintype "passive"))
      (node (ref "C408") (pin "2") (pinfunction "2_2") (pintype "passive"))
      (node (ref "C409") (pin "2") (pinfunction "2_2") (pintype "passive"))
      (node (ref "C410") (pin "2") (pinfunction "2_2") (pintype "passive"))
      (node (ref "D201") (pin "C") (pinfunction "C_C") (pintype "passive"))
      (node (ref "D202") (pin "C") (pinfunction "C_C") (pintype "passive"))
      (node (ref "J1") (pin "GND") (pinfunction "GND_GND") (pintype "passive"))
      (node (ref "J1") (pin "GND@2") (pinfunction "GND_GND@2") (pintype "passive"))
      (node (ref "JP101") (pin "4") (pinfunction "4_4") (pintype "passive"))
      (node (ref "JP102") (pin "P$6") (pinfunction "GND_P$6") (pintype "passive"))
      (node (ref "LED+") (pin "C") (pinfunction "C_C") (pintype "passive"))
      (node (ref "LED-") (pin "C") (pinfunction "C_C") (pintype "passive"))
      (node (ref "LEDU") (pin "C") (pinfunction "C_C") (pintype "passive"))
      (node (ref "LEDV") (pin "C") (pinfunction "C_C") (pintype "passive"))
      (node (ref "LEDW") (pin "C") (pinfunction "C_C") (pintype "passive"))
      (node (ref "R101") (pin "1") (pinfunction "1_1") (pintype "passive"))
      (node (ref "R203") (pin "1") (pinfunction "1_1") (pintype "passive"))
      (node (ref "R204") (pin "1") (pinfunction "1_1") (pintype "passive"))
      (node (ref "R206") (pin "1") (pinfunction "1_1") (pintype "passive"))
      (node (ref "R310") (pin "1") (pinfunction "1_1") (pintype "passive"))
      (node (ref "R311") (pin "1") (pinfunction "1_1") (pintype "passive"))
      (node (ref "R312") (pin "2") (pinfunction "2_2") (pintype "passive"))
      (node (ref "R408") (pin "2") (pinfunction "2_2") (pintype "passive"))
      (node (ref "R410") (pin "2") (pinfunction "2_2") (pintype "passive"))
      (node (ref "R415") (pin "2") (pinfunction "2_2") (pintype "passive"))
      (node (ref "R416") (pin "2") (pinfunction "2_2") (pintype "passive"))
      (node (ref "R417") (pin "2") (pinfunction "2_2") (pintype "passive"))
      (node (ref "U100") (pin "16") (pinfunction "VSS_16") (pintype "power_in"))
      (node (ref "U100") (pin "32") (pinfunction "VSS_32") (pintype "power_in"))
      (node (ref "U101") (pin "2") (pinfunction "GND_2") (pintype "power_in"))
      (node (ref "U200") (pin "10") (pinfunction "PGND_10") (pintype "power_in"))
      (node (ref "U200") (pin "4") (pinfunction "GND_4") (pintype "power_in"))
      (node (ref "U300") (pin "7") (pinfunction "GND_7") (pintype "power_in"))
      (node (ref "U300") (pin "EPAD") (pinfunction "GND_EPAD") (pintype "power_in"))
      (node (ref "U301") (pin "VCC-") (pinfunction "GND_VCC-") (pintype "bidirectional"))
      (node (ref "U302") (pin "13") (pinfunction "GND_13") (pintype "power_in"))
      (node (ref "U302") (pin "5") (pinfunction "TEST_5") (pintype "power_in"))
      (node (ref "U400") (pin "15") (pinfunction "TEST0_15") (pintype "bidirectional"))
      (node (ref "U400") (pin "16") (pinfunction "TEST1_16") (pintype "bidirectional"))
      (node (ref "U400") (pin "7") (pinfunction "GND_7") (pintype "power_in"))
      (node (ref "U400") (pin "EPAD") (pinfunction "GND_EPAD") (pintype "power_in"))
      (node (ref "U401") (pin "VCC-") (pinfunction "GND_VCC-") (pintype "bidirectional"))
      (node (ref "X101") (pin "2") (pinfunction "SHIELD_2") (pintype "power_in"))
      (node (ref "X101") (pin "4") (pinfunction "SHIELD_4") (pintype "power_in"))
    )
    (net (code "8") (name "NRESET") (class "Default")
      (node (ref "J1") (pin "!RESET") (pinfunction "~{RESET}_!RESET") (pintype "passive"))
      (node (ref "U100") (pin "4") (pinfunction "NRST_4") (pintype "bidirectional"))
    )
    (net (code "9") (name "Net-(C306-Pad1)") (class "Default")
      (node (ref "C306") (pin "1") (pinfunction "1_1") (pintype "passive"))
      (node (ref "R308") (pin "1") (pinfunction "1_1") (pintype "passive"))
      (node (ref "R309") (pin "2") (pinfunction "2_2") (pintype "passive"))
      (node (ref "U301") (pin "IN+") (pinfunction "IN+_IN+") (pintype "bidirectional"))
    )
    (net (code "10") (name "Net-(C307-Pad1)") (class "Default")
      (node (ref "C307") (pin "1") (pinfunction "1_1") (pintype "passive"))
      (node (ref "R312") (pin "1") (pinfunction "1_1") (pintype "passive"))
      (node (ref "R313") (pin "2") (pinfunction "2_2") (pintype "passive"))
      (node (ref "U301") (pin "IN-") (pinfunction "IN-_IN-") (pintype "bidirectional"))
    )
    (net (code "11") (name "Net-(C307-Pad2)") (class "Default")
      (node (ref "C307") (pin "2") (pinfunction "2_2") (pintype "passive"))
      (node (ref "R313") (pin "1") (pinfunction "1_1") (pintype "passive"))
      (node (ref "R314") (pin "2") (pinfunction "2_2") (pintype "passive"))
      (node (ref "U301") (pin "OUT") (pinfunction "OUT_OUT") (pintype "bidirectional"))
    )
    (net (code "12") (name "Net-(C406-Pad2)") (class "Default")
      (node (ref "C406") (pin "2") (pinfunction "2_2") (pintype "passive"))
      (node (ref "R407") (pin "2") (pinfunction "2_2") (pintype "passive"))
    )
    (net (code "13") (name "Net-(C408-Pad1)") (class "Default")
      (node (ref "C408") (pin "1") (pinfunction "1_1") (pintype "passive"))
      (node (ref "R413") (pin "1") (pinfunction "1_1") (pintype "passive"))
      (node (ref "R414") (pin "2") (pinfunction "2_2") (pintype "passive"))
      (node (ref "U401") (pin "IN+") (pinfunction "IN+_IN+") (pintype "bidirectional"))
    )
    (net (code "14") (name "Net-(C411-Pad1)") (class "Default")
      (node (ref "C411") (pin "1") (pinfunction "1_1") (pintype "passive"))
      (node (ref "R417") (pin "1") (pinfunction "1_1") (pintype "passive"))
      (node (ref "R418") (pin "2") (pinfunction "2_2") (pintype "passive"))
      (node (ref "U401") (pin "IN-") (pinfunction "IN-_IN-") (pintype "bidirectional"))
    )
    (net (code "15") (name "Net-(C411-Pad2)") (class "Default")
      (node (ref "C411") (pin "2") (pinfunction "2_2") (pintype "passive"))
      (node (ref "R418") (pin "1") (pinfunction "1_1") (pintype "passive"))
      (node (ref "R419") (pin "2") (pinfunction "2_2") (pintype "passive"))
      (node (ref "U401") (pin "OUT") (pinfunction "OUT_OUT") (pintype "bidirectional"))
    )
    (net (code "16") (name "Net-(D201-PadA)") (class "Default")
      (node (ref "D201") (pin "A") (pinfunction "A_A") (pintype "passive"))
      (node (ref "R208") (pin "1") (pinfunction "1_1") (pintype "passive"))
    )
    (net (code "17") (name "Net-(D202-PadA)") (class "Default")
      (node (ref "D202") (pin "A") (pinfunction "A_A") (pintype "passive"))
      (node (ref "R209") (pin "1") (pinfunction "1_1") (pintype "passive"))
    )
    (net (code "18") (name "Net-(LED+-PadA)") (class "Default")
      (node (ref "LED+") (pin "A") (pinfunction "A_A") (pintype "passive"))
      (node (ref "R411") (pin "1") (pinfunction "1_1") (pintype "passive"))
    )
    (net (code "19") (name "Net-(LED--PadA)") (class "Default")
      (node (ref "LED-") (pin "A") (pinfunction "A_A") (pintype "passive"))
      (node (ref "R412") (pin "2") (pinfunction "2_2") (pintype "passive"))
    )
    (net (code "20") (name "Net-(LEDU-PadA)") (class "Default")
      (node (ref "LEDU") (pin "A") (pinfunction "A_A") (pintype "passive"))
      (node (ref "R305") (pin "1") (pinfunction "1_1") (pintype "passive"))
    )
    (net (code "21") (name "Net-(LEDV-PadA)") (class "Default")
      (node (ref "LEDV") (pin "A") (pinfunction "A_A") (pintype "passive"))
      (node (ref "R306") (pin "1") (pinfunction "1_1") (pintype "passive"))
    )
    (net (code "22") (name "Net-(LEDW-PadA)") (class "Default")
      (node (ref "LEDW") (pin "A") (pinfunction "A_A") (pintype "passive"))
      (node (ref "R307") (pin "1") (pinfunction "1_1") (pintype "passive"))
    )
    (net (code "23") (name "Net-(U100-PB8-BOOT0)") (class "Default")
      (node (ref "R101") (pin "2") (pinfunction "2_2") (pintype "passive"))
      (node (ref "TP101") (pin "1") (pinfunction "1_1") (pintype "passive"))
      (node (ref "U100") (pin "31") (pinfunction "PB8-BOOT0_31") (pintype "bidirectional"))
    )
    (net (code "24") (name "Net-(U100-PF0-OSC_IN)") (class "Default")
      (node (ref "C105") (pin "1") (pinfunction "1_1") (pintype "passive"))
      (node (ref "U100") (pin "2") (pinfunction "PF0-OSC_IN_2") (pintype "bidirectional"))
      (node (ref "X101") (pin "1") (pinfunction "1_1") (pintype "passive"))
    )
    (net (code "25") (name "Net-(U100-PF1-OSC_OUT)") (class "Default")
      (node (ref "C104") (pin "1") (pinfunction "1_1") (pintype "passive"))
      (node (ref "U100") (pin "3") (pinfunction "PF1-OSC_OUT_3") (pintype "bidirectional"))
      (node (ref "X101") (pin "3") (pinfunction "2_3") (pintype "passive"))
    )
    (net (code "26") (name "Net-(U200-EN)") (class "Default")
      (node (ref "R202") (pin "1") (pinfunction "1_1") (pintype "passive"))
      (node (ref "R203") (pin "2") (pinfunction "2_2") (pintype "passive"))
      (node (ref "TP201") (pin "1") (pinfunction "1_1") (pintype "passive"))
      (node (ref "U200") (pin "1") (pinfunction "PS/SYNC_1") (pintype "input"))
      (node (ref "U200") (pin "14") (pinfunction "EN_14") (pintype "input"))
    )
    (net (code "27") (name "Net-(U200-FB)") (class "Default")
      (node (ref "R205") (pin "1") (pinfunction "1_1") (pintype "passive"))
      (node (ref "R206") (pin "2") (pinfunction "2_2") (pintype "passive"))
      (node (ref "U200") (pin "5") (pinfunction "FB_5") (pintype "passive"))
    )
    (net (code "28") (name "Net-(U200-FB2)") (class "Default")
      (node (ref "TP204") (pin "1") (pinfunction "1_1") (pintype "passive"))
      (node (ref "U200") (pin "6") (pinfunction "FB2_6") (pintype "passive"))
    )
    (net (code "29") (name "Net-(U200-L1)") (class "Default")
      (node (ref "L201") (pin "1") (pinfunction "1_1") (pintype "passive"))
      (node (ref "U200") (pin "11") (pinfunction "L1_11") (pintype "passive"))
    )
    (net (code "30") (name "Net-(U200-L2)") (class "Default")
      (node (ref "L201") (pin "2") (pinfunction "2_2") (pintype "passive"))
      (node (ref "U200") (pin "9") (pinfunction "L2_9") (pintype "passive"))
    )
    (net (code "31") (name "Net-(U200-PG)") (class "Default")
      (node (ref "R207") (pin "1") (pinfunction "1_1") (pintype "passive"))
      (node (ref "TP203") (pin "1") (pinfunction "1_1") (pintype "passive"))
      (node (ref "U200") (pin "2") (pinfunction "PG_2") (pintype "open_collector"))
    )
    (net (code "32") (name "Net-(U200-VAUX)") (class "Default")
      (node (ref "C204") (pin "1") (pinfunction "1_1") (pintype "passive"))
      (node (ref "U200") (pin "3") (pinfunction "VAUX_3") (pintype "output"))
    )
    (net (code "33") (name "Net-(U200-VIN)") (class "Default")
      (node (ref "C201") (pin "1") (pinfunction "1_1") (pintype "passive"))
      (node (ref "C202") (pin "1") (pinfunction "1_1") (pintype "passive"))
      (node (ref "C203") (pin "1") (pinfunction "1_1") (pintype "passive"))
      (node (ref "R201") (pin "1") (pinfunction "1_1") (pintype "passive"))
      (node (ref "R202") (pin "2") (pinfunction "2_2") (pintype "passive"))
      (node (ref "U200") (pin "12-13") (pinfunction "VIN_12-13") (pintype "power_in"))
    )
    (net (code "34") (name "Net-(U200-VSEL)") (class "Default")
      (node (ref "R204") (pin "2") (pinfunction "2_2") (pintype "passive"))
      (node (ref "TP202") (pin "1") (pinfunction "1_1") (pintype "passive"))
      (node (ref "U200") (pin "15") (pinfunction "VSEL_15") (pintype "input"))
    )
    (net (code "35") (name "Net-(U300-OUTU)") (class "Default")
      (node (ref "JP301") (pin "1") (pinfunction "1_1") (pintype "passive"))
      (node (ref "R305") (pin "2") (pinfunction "2_2") (pintype "passive"))
      (node (ref "U300") (pin "3") (pinfunction "OUTU_3") (pintype "output"))
    )
    (net (code "36") (name "Net-(U300-OUTV)") (class "Default")
      (node (ref "JP301") (pin "2") (pinfunction "2_2") (pintype "passive"))
      (node (ref "R306") (pin "2") (pinfunction "2_2") (pintype "passive"))
      (node (ref "U300") (pin "8") (pinfunction "OUTV_8") (pintype "output"))
    )
    (net (code "37") (name "Net-(U300-OUTW)") (class "Default")
      (node (ref "JP301") (pin "3") (pinfunction "3_3") (pintype "passive"))
      (node (ref "R307") (pin "2") (pinfunction "2_2") (pintype "passive"))
      (node (ref "U300") (pin "10") (pinfunction "OUTW_10") (pintype "output"))
    )
    (net (code "38") (name "Net-(U300-SENSEU)") (class "Default")
      (node (ref "R309") (pin "1") (pinfunction "1_1") (pintype "passive"))
      (node (ref "R310") (pin "2") (pinfunction "2_2") (pintype "passive"))
      (node (ref "R311") (pin "2") (pinfunction "2_2") (pintype "passive"))
      (node (ref "U300") (pin "4") (pinfunction "SENSEU_4") (pintype "output"))
      (node (ref "U300") (pin "9") (pinfunction "SENSEVW_9") (pintype "output"))
    )
    (net (code "39") (name "Net-(U300-VS)") (class "Default")
      (node (ref "C301") (pin "1") (pinfunction "1_1") (pintype "passive"))
      (node (ref "C302") (pin "1") (pinfunction "1_1") (pintype "passive"))
      (node (ref "C303") (pin "1") (pinfunction "1_1") (pintype "passive"))
      (node (ref "R303") (pin "1") (pinfunction "1_1") (pintype "passive"))
      (node (ref "R304") (pin "1") (pinfunction "1_1") (pintype "passive"))
      (node (ref "U300") (pin "6") (pinfunction "VS_6") (pintype "power_in"))
    )
    (net (code "40") (name "Net-(U302-A)") (class "Default")
      (node (ref "JP302") (pin "2") (pinfunction "2_2") (pintype "passive"))
      (node (ref "U302") (pin "7") (pinfunction "A_7") (pintype "output"))
    )
    (net (code "41") (name "Net-(U302-B)") (class "Default")
      (node (ref "JP302") (pin "1") (pinfunction "1_1") (pintype "passive"))
      (node (ref "U302") (pin "6") (pinfunction "B_6") (pintype "output"))
    )
    (net (code "42") (name "Net-(U302-MOSI)") (class "Default")
      (node (ref "R315") (pin "2") (pinfunction "2_2") (pintype "passive"))
      (node (ref "U302") (pin "4") (pinfunction "MOSI_4") (pintype "input"))
    )
    (net (code "43") (name "Net-(U400-OUTA1)") (class "Default")
      (node (ref "JP401") (pin "1") (pinfunction "1_1") (pintype "passive"))
      (node (ref "R411") (pin "2") (pinfunction "2_2") (pintype "passive"))
      (node (ref "U400") (pin "10") (pinfunction "OUTB1_10") (pintype "output"))
      (node (ref "U400") (pin "3") (pinfunction "OUTA1_3") (pintype "output"))
    )
    (net (code "44") (name "Net-(U400-OUTA2)") (class "Default")
      (node (ref "JP401") (pin "2") (pinfunction "2_2") (pintype "passive"))
      (node (ref "R412") (pin "1") (pinfunction "1_1") (pintype "passive"))
      (node (ref "U400") (pin "5") (pinfunction "OUTA2_5") (pintype "output"))
      (node (ref "U400") (pin "8") (pinfunction "OUTB2_8") (pintype "output"))
    )
    (net (code "45") (name "Net-(U400-PH)") (class "Default")
      (node (ref "R405") (pin "1") (pinfunction "1_1") (pintype "passive"))
      (node (ref "U400") (pin "1") (pinfunction "PH_1") (pintype "input"))
    )
    (net (code "46") (name "Net-(U400-PWM)") (class "Default")
      (node (ref "R406") (pin "1") (pinfunction "1_1") (pintype "passive"))
      (node (ref "U400") (pin "2") (pinfunction "PWM_2") (pintype "input"))
    )
    (net (code "47") (name "Net-(U400-REF)") (class "Default")
      (node (ref "C407") (pin "2") (pinfunction "2_2") (pintype "passive"))
      (node (ref "R409") (pin "2") (pinfunction "2_2") (pintype "passive"))
      (node (ref "R410") (pin "1") (pinfunction "1_1") (pintype "passive"))
      (node (ref "U400") (pin "11") (pinfunction "REF_11") (pintype "passive"))
    )
    (net (code "48") (name "Net-(U400-SENSEA)") (class "Default")
      (node (ref "R414") (pin "1") (pinfunction "1_1") (pintype "passive"))
      (node (ref "R415") (pin "1") (pinfunction "1_1") (pintype "passive"))
      (node (ref "R416") (pin "1") (pinfunction "1_1") (pintype "passive"))
      (node (ref "U400") (pin "4") (pinfunction "SENSEA_4") (pintype "output"))
      (node (ref "U400") (pin "9") (pinfunction "SENSEB_9") (pintype "output"))
    )
    (net (code "49") (name "Net-(U400-TOFF)") (class "Default")
      (node (ref "R407") (pin "1") (pinfunction "1_1") (pintype "passive"))
      (node (ref "R408") (pin "1") (pinfunction "1_1") (pintype "passive"))
      (node (ref "U400") (pin "12") (pinfunction "TOFF_12") (pintype "passive"))
    )
    (net (code "50") (name "Net-(U400-VS)") (class "Default")
      (node (ref "C401") (pin "1") (pinfunction "1_1") (pintype "passive"))
      (node (ref "C402") (pin "1") (pinfunction "1_1") (pintype "passive"))
      (node (ref "C403") (pin "1") (pinfunction "1_1") (pintype "passive"))
      (node (ref "R403") (pin "1") (pinfunction "1_1") (pintype "passive"))
      (node (ref "R404") (pin "1") (pinfunction "1_1") (pintype "passive"))
      (node (ref "U400") (pin "6") (pinfunction "VS_6") (pintype "power_in"))
    )
    (net (code "51") (name "PA0{slash}CURR_FDB_MAG") (class "Default")
      (node (ref "R419") (pin "1") (pinfunction "1_1") (pintype "passive"))
      (node (ref "TP1") (pin "1") (pinfunction "1_1") (pintype "passive"))
      (node (ref "U100") (pin "6") (pinfunction "PA0_6") (pintype "bidirectional"))
    )
    (net (code "52") (name "PA1{slash}CURR_FDB_BLDC") (class "Default")
      (node (ref "R314") (pin "1") (pinfunction "1_1") (pintype "passive"))
      (node (ref "TP2") (pin "1") (pinfunction "1_1") (pintype "passive"))
      (node (ref "U100") (pin "7") (pinfunction "PA1_7") (pintype "bidirectional"))
    )
    (net (code "53") (name "PA2{slash}USART2_TX") (class "Default")
      (node (ref "JP102") (pin "P$2") (pinfunction "TXO_P$2") (pintype "passive"))
      (node (ref "U100") (pin "8") (pinfunction "PA2_8") (pintype "bidirectional"))
    )
    (net (code "54") (name "PA3{slash}USART2_RX") (class "Default")
      (node (ref "JP102") (pin "P$3") (pinfunction "RXI_P$3") (pintype "passive"))
      (node (ref "U100") (pin "9") (pinfunction "PA3_9") (pintype "bidirectional"))
    )
    (net (code "55") (name "PA4{slash}FAULT_BLDC") (class "Default")
      (node (ref "C305") (pin "2") (pinfunction "2_2") (pintype "passive"))
      (node (ref "R302") (pin "1") (pinfunction "1_1") (pintype "passive"))
      (node (ref "U100") (pin "10") (pinfunction "PA4_10") (pintype "bidirectional"))
      (node (ref "U300") (pin "13") (pinfunction "EN/FAULT_13") (pintype "bidirectional"))
    )
    (net (code "56") (name "PA5{slash}SPI1_SCK") (class "Default")
      (node (ref "U100") (pin "11") (pinfunction "PA5_11") (pintype "bidirectional"))
      (node (ref "U302") (pin "2") (pinfunction "SCLK_2") (pintype "input"))
    )
    (net (code "57") (name "PA6{slash}CAN_LSTN") (class "Default")
      (node (ref "U100") (pin "12") (pinfunction "PA6_12") (pintype "bidirectional"))
      (node (ref "U101") (pin "8") (pinfunction "S_8") (pintype "input"))
    )
    (net (code "58") (name "PA7{slash}INUL") (class "Default")
      (node (ref "TP3") (pin "1") (pinfunction "1_1") (pintype "passive"))
      (node (ref "U100") (pin "13") (pinfunction "PA7_13") (pintype "bidirectional"))
      (node (ref "U300") (pin "1") (pinfunction "INUL_1") (pintype "input"))
    )
    (net (code "59") (name "PA8{slash}INUH{slash}PWM_MAG") (class "Default")
      (node (ref "R406") (pin "2") (pinfunction "2_2") (pintype "passive"))
      (node (ref "TP4") (pin "1") (pinfunction "1_1") (pintype "passive"))
      (node (ref "U100") (pin "18") (pinfunction "PA8_18") (pintype "bidirectional"))
      (node (ref "U300") (pin "2") (pinfunction "INUH_2") (pintype "input"))
    )
    (net (code "60") (name "PA9{slash}INVH{slash}DIR_MAG") (class "Default")
      (node (ref "R405") (pin "2") (pinfunction "2_2") (pintype "passive"))
      (node (ref "TP5") (pin "1") (pinfunction "1_1") (pintype "passive"))
      (node (ref "U100") (pin "19") (pinfunction "PA9_19") (pintype "bidirectional"))
      (node (ref "U300") (pin "16") (pinfunction "INVH_16") (pintype "input"))
    )
    (net (code "61") (name "PA10{slash}INWH") (class "Default")
      (node (ref "TP6") (pin "1") (pinfunction "1_1") (pintype "passive"))
      (node (ref "U100") (pin "20") (pinfunction "PA10_20") (pintype "bidirectional"))
      (node (ref "U300") (pin "12") (pinfunction "INWH_12") (pintype "input"))
    )
    (net (code "62") (name "PA15{slash}SPI1_NSS") (class "Default")
      (node (ref "U100") (pin "25") (pinfunction "PA15_25") (pintype "bidirectional"))
      (node (ref "U302") (pin "1") (pinfunction "CSN_1") (pintype "input"))
    )
    (net (code "63") (name "PB0{slash}INVL") (class "Default")
      (node (ref "TP7") (pin "1") (pinfunction "1_1") (pintype "passive"))
      (node (ref "U100") (pin "14") (pinfunction "PB0_14") (pintype "bidirectional"))
      (node (ref "U300") (pin "15") (pinfunction "INVL_15") (pintype "input"))
    )
    (net (code "64") (name "PB1{slash}INWL") (class "Default")
      (node (ref "TP8") (pin "1") (pinfunction "1_1") (pintype "passive"))
      (node (ref "U100") (pin "15") (pinfunction "PB1_15") (pintype "bidirectional"))
      (node (ref "U300") (pin "11") (pinfunction "INWL_11") (pintype "input"))
    )
    (net (code "65") (name "PB3{slash}EN_MAG") (class "Default")
      (node (ref "R402") (pin "2") (pinfunction "2_2") (pintype "passive"))
      (node (ref "U100") (pin "26") (pinfunction "PB3_26") (pintype "bidirectional"))
    )
    (net (code "66") (name "PB4{slash}SPI1_MISO") (class "Default")
      (node (ref "U100") (pin "27") (pinfunction "PB4_27") (pintype "bidirectional"))
      (node (ref "U302") (pin "3") (pinfunction "MISO_3") (pintype "output"))
    )
    (net (code "67") (name "PB5") (class "Default")
      (node (ref "U100") (pin "28") (pinfunction "PB5_28") (pintype "bidirectional"))
    )
    (net (code "68") (name "PB6{slash}EN_BLDC") (class "Default")
      (node (ref "R302") (pin "2") (pinfunction "2_2") (pintype "passive"))
      (node (ref "U100") (pin "29") (pinfunction "PB6_29") (pintype "bidirectional"))
    )
    (net (code "69") (name "PB7{slash}FAULT_MAG") (class "Default")
      (node (ref "C405") (pin "2") (pinfunction "2_2") (pintype "passive"))
      (node (ref "R402") (pin "1") (pinfunction "1_1") (pintype "passive"))
      (node (ref "U100") (pin "30") (pinfunction "PB7_30") (pintype "bidirectional"))
      (node (ref "U400") (pin "13") (pinfunction "EN/FAULT_13") (pintype "bidirectional"))
    )
    (net (code "70") (name "STBY{slash}RESET_BLDC") (class "Default")
      (node (ref "C304") (pin "2") (pinfunction "2_2") (pintype "passive"))
      (node (ref "R301") (pin "1") (pinfunction "1_1") (pintype "passive"))
      (node (ref "TP9") (pin "TP") (pinfunction "TP_TP") (pintype "input"))
      (node (ref "U300") (pin "14") (pinfunction "STBY/RESET_14") (pintype "input"))
    )
    (net (code "71") (name "STBY{slash}RESET_MAG") (class "Default")
      (node (ref "C404") (pin "2") (pinfunction "2_2") (pintype "passive"))
      (node (ref "R401") (pin "1") (pinfunction "1_1") (pintype "passive"))
      (node (ref "TP10") (pin "TP") (pinfunction "TP_TP") (pintype "input"))
      (node (ref "U400") (pin "14") (pinfunction "STBY/RESET_14") (pintype "bidirectional"))
    )
    (net (code "72") (name "SWCLK") (class "Default")
      (node (ref "J1") (pin "SWDCLK") (pinfunction "SWDCLK/TCK_SWDCLK") (pintype "passive"))
      (node (ref "U100") (pin "24") (pinfunction "PA14-SWCLK_24") (pintype "bidirectional"))
    )
    (net (code "73") (name "SWDIO") (class "Default")
      (node (ref "J1") (pin "SWDIO") (pinfunction "SWDIO/TMS_SWDIO") (pintype "passive"))
      (node (ref "U100") (pin "23") (pinfunction "PA13-SWDIO_23") (pintype "bidirectional"))
    )
    (net (code "74") (name "V_BATT") (class "Default")
      (node (ref "JP101") (pin "1") (pinfunction "1_1") (pintype "passive"))
      (node (ref "R201") (pin "2") (pinfunction "2_2") (pintype "passive"))
      (node (ref "R208") (pin "2") (pinfunction "2_2") (pintype "passive"))
      (node (ref "R303") (pin "2") (pinfunction "2_2") (pintype "passive"))
      (node (ref "R403") (pin "2") (pinfunction "2_2") (pintype "passive"))
    )
    (net (code "75") (name "unconnected-(J1-NC{slash}TDI-PadNC)") (class "Default")
      (node (ref "J1") (pin "NC") (pinfunction "NC/TDI_NC") (pintype "passive"))
    )
    (net (code "76") (name "unconnected-(J1-PadGNDDET)") (class "Default")
      (node (ref "J1") (pin "GNDDET") (pinfunction "GNDDET_GNDDET") (pintype "passive"))
    )
    (net (code "77") (name "unconnected-(J1-SWO{slash}TDO-PadSWO)") (class "Default")
      (node (ref "J1") (pin "SWO") (pinfunction "SWO/TDO_SWO") (pintype "passive"))
    )
    (net (code "78") (name "unconnected-(JP102-CTS-PadP$5)") (class "Default")
      (node (ref "JP102") (pin "P$5") (pinfunction "CTS_P$5") (pintype "passive"))
    )
    (net (code "79") (name "unconnected-(JP102-DTR-PadP$1)") (class "Default")
      (node (ref "JP102") (pin "P$1") (pinfunction "DTR_P$1") (pintype "passive"))
    )
    (net (code "80") (name "unconnected-(JP102-VCC-PadP$4)") (class "Default")
      (node (ref "JP102") (pin "P$4") (pinfunction "VCC_P$4") (pintype "passive"))
    )
    (net (code "81") (name "unconnected-(U302-I{slash}PWM-Pad14)") (class "Default")
      (node (ref "U302") (pin "14") (pinfunction "I/PWM_14") (pintype "output"))
    )
    (net (code "82") (name "unconnected-(U302-U-Pad10)") (class "Default")
      (node (ref "U302") (pin "10") (pinfunction "U_10") (pintype "output"))
    )
    (net (code "83") (name "unconnected-(U302-V-Pad9)") (class "Default")
      (node (ref "U302") (pin "9") (pinfunction "V_9") (pintype "output"))
    )
    (net (code "84") (name "unconnected-(U302-W{slash}PWM-Pad8)") (class "Default")
      (node (ref "U302") (pin "8") (pinfunction "W/PWM_8") (pintype "output"))
    )
  )
)
